# 01_MAIN.net
KiCad netlist of a schematic drawn in Altium Designer
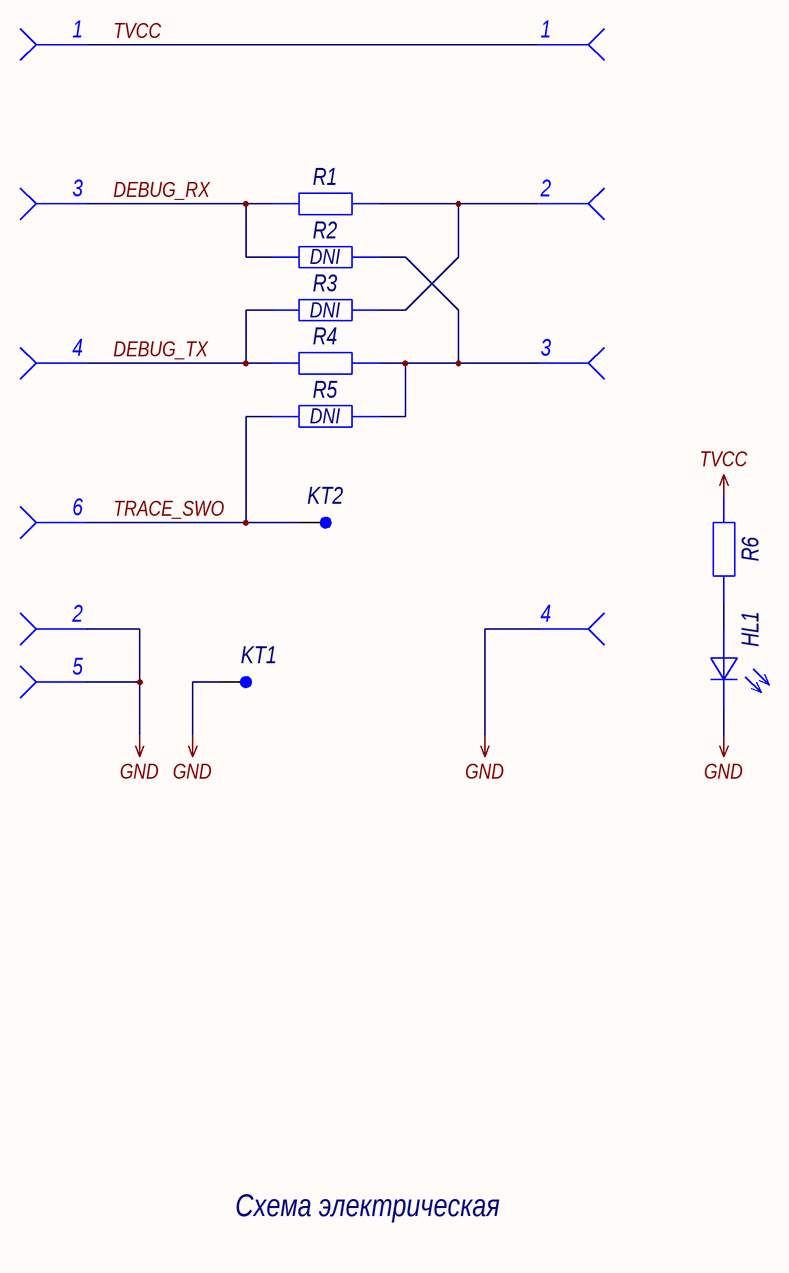
[diagram p0: 01_MAIN.SchDoc]

(export (version "E")
  (design (tool "Eeschema 10.0.6"))
  (components
    (comp (ref "HL1")
      (value "TVCC")
      (footprint "LD0402_L")
      (fields
        (field (name "PART NUMBER") "KPHHS-1005QBC-D-V")
        (field (name "MANUFACTURER") "Kingbright")
        (field (name "PUBLISHER") "Andrew Danich")
      )
      (libsource (lib "ADLib") (part "Led-1"))
    )
    (comp (ref "KT1")
      (value "Text")
      (footprint "TP-SMT-R-0.8mm")
      (fields (field (name "PART NUMBER") "TestPoint-SMT-GND") (field (name "PUBLISHER") "Andrew Danich"))
      (libsource (lib "ADLib") (part "TP-S-1"))
    )
    (comp (ref "KT2")
      (value "SWO")
      (footprint "TP-SMT-C-0.5mm")
      (fields (field (name "PART NUMBER") "TestPoint-SMT") (field (name "PUBLISHER") "Andrew Danich"))
      (libsource (lib "ADLib") (part "TP-S-1"))
    )
    (comp (ref "R1")
      (value "Resistor")
      (footprint "R0402_L")
      (fields
        (field (name "PART NUMBER") "RC0402JR-070RL")
        (field (name "TOLERANCE") "±5%")
        (field (name "MANUFACTURER") "Yageo")
        (field (name "PUBLISHER") "Andrew Danich")
      )
      (libsource (lib "ADLib") (part "Resistor"))
    )
    (comp (ref "R2")
      (value "Resistor")
      (footprint "R0402_L")
      (fields
        (field (name "PART NUMBER") "RC0402JR-070RL")
        (field (name "TOLERANCE") "±5%")
        (field (name "MANUFACTURER") "Yageo")
        (field (name "PUBLISHER") "Andrew Danich")
      )
      (libsource (lib "ADLib") (part "Resistor"))
    )
    (comp (ref "R3")
      (value "Resistor")
      (footprint "R0402_L")
      (fields
        (field (name "PART NUMBER") "RC0402JR-070RL")
        (field (name "TOLERANCE") "±5%")
        (field (name "MANUFACTURER") "Yageo")
        (field (name "PUBLISHER") "Andrew Danich")
      )
      (libsource (lib "ADLib") (part "Resistor"))
    )
    (comp (ref "R4")
      (value "Resistor")
      (footprint "R0402_L")
      (fields
        (field (name "PART NUMBER") "RC0402JR-070RL")
        (field (name "TOLERANCE") "±5%")
        (field (name "MANUFACTURER") "Yageo")
        (field (name "PUBLISHER") "Andrew Danich")
      )
      (libsource (lib "ADLib") (part "Resistor"))
    )
    (comp (ref "R5")
      (value "Resistor")
      (footprint "R0402_L")
      (fields
        (field (name "PART NUMBER") "RC0402JR-070RL")
        (field (name "TOLERANCE") "±5%")
        (field (name "MANUFACTURER") "Yageo")
        (field (name "PUBLISHER") "Andrew Danich")
      )
      (libsource (lib "ADLib") (part "Resistor"))
    )
    (comp (ref "R6")
      (value "Resistor")
      (footprint "R0402_L")
      (fields
        (field (name "PART NUMBER") "RC0402JR-0710KL")
        (field (name "TOLERANCE") "±5%")
        (field (name "MANUFACTURER") "Yageo")
        (field (name "PUBLISHER") "Andrew Danich")
      )
      (libsource (lib "ADLib") (part "Resistor"))
    )
    (comp (ref "XS1")
      (value "DEBUG")
      (footprint "XF2M-0615-1A")
      (fields
        (field (name "PART NUMBER") "XF2M-0615-1A")
        (field (name "MANUFACTURER") "Omron Electronics")
        (field (name "PUBLISHER") "Viktor Klishin")
      )
      (libsource (lib "ADLib") (part "Con-6-F_S"))
    )
    (comp (ref "XS2")
      (value "PBS-4_S")
      (footprint "PBS-4")
      (fields (field (name "PUBLISHER") "Andrew Danich"))
      (libsource (lib "Schlib") (part "PBS-4_S"))
    )
  )
  (nets
    (net (code "1") (name "/DEBUG_RX") (class "Default")
      (node (ref "R1") (pin "1") (pinfunction "1_1") (pintype "passive"))
      (node (ref "R2") (pin "1") (pinfunction "1_1") (pintype "passive"))
      (node (ref "XS1") (pin "3") (pintype "passive"))
    )
    (net (code "2") (name "/DEBUG_TX") (class "Default")
      (node (ref "R3") (pin "1") (pinfunction "1_1") (pintype "passive"))
      (node (ref "R4") (pin "1") (pinfunction "1_1") (pintype "passive"))
      (node (ref "XS1") (pin "4") (pintype "passive"))
    )
    (net (code "3") (name "/TRACE_SWO") (class "Default")
      (node (ref "KT2") (pin "1") (pinfunction "1_1") (pintype "passive"))
      (node (ref "R5") (pin "1") (pinfunction "1_1") (pintype "passive"))
      (node (ref "XS1") (pin "6") (pintype "passive"))
    )
    (net (code "4") (name "GND") (class "Default")
      (node (ref "HL1") (pin "2") (pinfunction "К_2") (pintype "passive"))
      (node (ref "KT1") (pin "1") (pinfunction "1_1") (pintype "passive"))
      (node (ref "XS1") (pin "2") (pintype "passive"))
      (node (ref "XS1") (pin "5") (pintype "passive"))
      (node (ref "XS2") (pin "4") (pintype "passive"))
    )
    (net (code "5") (name "Net-(HL1-А)") (class "Default")
      (node (ref "HL1") (pin "1") (pinfunction "А_1") (pintype "passive"))
      (node (ref "R6") (pin "1") (pinfunction "1_1") (pintype "passive"))
    )
    (net (code "6") (name "Net-(R1-Pad2)") (class "Default")
      (node (ref "R1") (pin "2") (pinfunction "2_2") (pintype "passive"))
      (node (ref "R3") (pin "2") (pinfunction "2_2") (pintype "passive"))
      (node (ref "XS2") (pin "2") (pintype "passive"))
    )
    (net (code "7") (name "Net-(R2-Pad2)") (class "Default")
      (node (ref "R2") (pin "2") (pinfunction "2_2") (pintype "passive"))
      (node (ref "R4") (pin "2") (pinfunction "2_2") (pintype "passive"))
      (node (ref "R5") (pin "2") (pinfunction "2_2") (pintype "passive"))
      (node (ref "XS2") (pin "3") (pintype "passive"))
    )
    (net (code "8") (name "TVCC") (class "Default")
      (node (ref "R6") (pin "2") (pinfunction "2_2") (pintype "passive"))
      (node (ref "XS1") (pin "1") (pintype "passive"))
      (node (ref "XS2") (pin "1") (pintype "passive"))
    )
  )
)
